# LPCDuino.net
KiCad netlist of a schematic drawn in Altium Designer
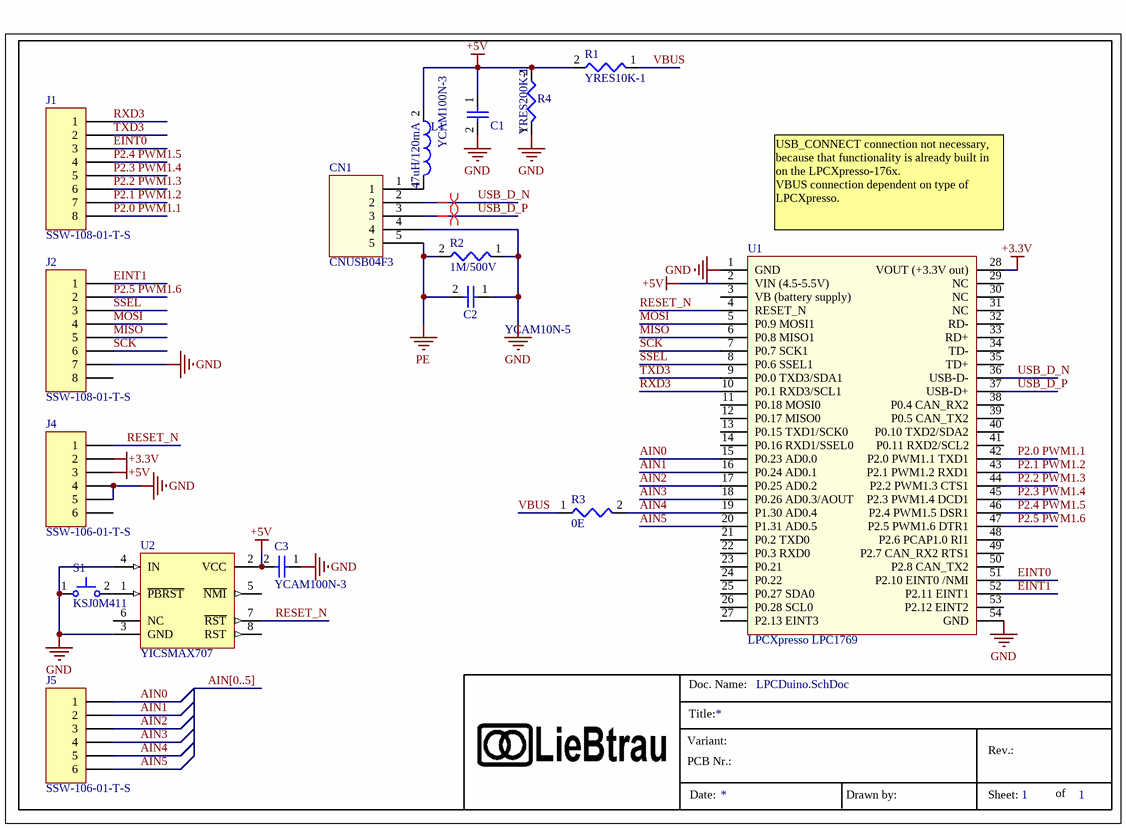
[diagram p0: LPCDuino.SchDoc]

(export (version "E")
  (design (tool "Eeschema 10.0.6"))
  (components
    (comp (ref "C1")
      (value "YCAM100N-3")
      (footprint "CA_0603")
      (libsource (lib "Testing") (part "CA_NONPOL"))
    )
    (comp (ref "C2")
      (value "YCAM10N-5")
      (footprint "CA_1206")
      (fields (field (name "MANUFACTURER") "Yageo (Phycomp)"))
      (libsource (lib "Testing") (part "CA_NONPOL"))
    )
    (comp (ref "C3")
      (value "YCAM100N-3")
      (footprint "CA_0603")
      (libsource (lib "Testing") (part "CA_NONPOL"))
    )
    (comp (ref "CN1")
      (value "CNUSB04F3")
      (footprint "CN_USB_B")
      (fields (field (name "MANUFACTURER") "TE Connectivity"))
      (libsource (lib "Testing") (part "CN_5P"))
    )
    (comp (ref "J1")
      (value "SSW-108-01-T-S")
      (footprint "CN_SOCKET8")
      (fields (field (name "MANUFACTURER") "Samtec"))
      (libsource (lib "Testing") (part "CN_8P"))
    )
    (comp (ref "J2")
      (value "SSW-108-01-T-S")
      (footprint "CN_SOCKET8")
      (fields (field (name "MANUFACTURER") "Samtec"))
      (libsource (lib "Testing") (part "CN_8P"))
    )
    (comp (ref "J4")
      (value "SSW-106-01-T-S")
      (footprint "CN_SOCKET6")
      (fields (field (name "MANUFACTURER") "Samtec"))
      (libsource (lib "Testing") (part "CN_6P"))
    )
    (comp (ref "J5")
      (value "SSW-106-01-T-S")
      (footprint "CN_SOCKET6")
      (fields (field (name "MANUFACTURER") "Samtec"))
      (libsource (lib "Testing") (part "CN_6P"))
    )
    (comp (ref "L1")
      (value "47uH/120mA")
      (footprint "CL_0805")
      (fields (field (name "PART NUMBER") "L0805C470MDWIT") (field (name "MANUFACTURER") "Kemet"))
      (libsource (lib "Testing") (part "CL_COIL"))
    )
    (comp (ref "R1")
      (value "YRES10K-1")
      (footprint "RE_0603")
      (description "Resistor")
      (libsource (lib "Testing") (part "RE_RES"))
    )
    (comp (ref "R2")
      (value "1M/500V")
      (footprint "RE_2010")
      (description "Resistor")
      (fields (field (name "PART NUMBER") "LHVC2010-1MFT4") (field (name "MANUFACTURER") "Welwyn"))
      (libsource (lib "Testing") (part "RE_RES"))
    )
    (comp (ref "R3")
      (value "0E")
      (footprint "RE_1206")
      (description "Resistor")
      (fields (field (name "PART NUMBER") "YRES0E") (field (name "MANUFACTURER") "Vishay Draloric"))
      (libsource (lib "Testing") (part "RE_RES"))
    )
    (comp (ref "R4")
      (value "YRES200K-1")
      (footprint "RE_0603")
      (description "Resistor")
      (libsource (lib "Testing") (part "RE_RES"))
    )
    (comp (ref "S1")
      (value "KSJ0M411")
      (footprint "SW_KSJ-M")
      (fields (field (name "MANUFACTURER") "C&K"))
      (libsource (lib "Testing") (part "SW_SPST"))
    )
    (comp (ref "U1")
      (value "LPCXpresso LPC1769")
      (footprint "MD_LPCXpresso")
      (fields (field (name "PART NUMBER") "OM13000") (field (name "MANUFACTURER") "NXP"))
      (libsource (lib "Testing") (part "IC_LPCXpresso_LPC1769"))
    )
    (comp (ref "U2")
      (value "YICSMAX707")
      (footprint "SC_SOIC8")
      (fields (field (name "MANUFACTURER") "Maxim"))
      (libsource (lib "Testing") (part "IC_MAX707"))
    )
  )
  (nets
    (net (code "1") (name "+3.3V") (class "Default")
      (node (ref "J4") (pin "2") (pinfunction "2_2") (pintype "passive"))
      (node (ref "U1") (pin "28") (pinfunction "VOUT_(+3.3V_out)_28") (pintype "passive"))
    )
    (net (code "2") (name "+5V") (class "Default")
      (node (ref "C1") (pin "1") (pinfunction "1_1") (pintype "passive"))
      (node (ref "C3") (pin "2") (pinfunction "2_2") (pintype "passive"))
      (node (ref "J4") (pin "3") (pinfunction "3_3") (pintype "passive"))
      (node (ref "L1") (pin "2") (pinfunction "2_2") (pintype "passive"))
      (node (ref "R1") (pin "2") (pinfunction "2_2") (pintype "passive"))
      (node (ref "R4") (pin "2") (pinfunction "2_2") (pintype "passive"))
      (node (ref "U1") (pin "2") (pinfunction "VIN_(4.5-5.5V)_2") (pintype "passive"))
      (node (ref "U2") (pin "2") (pinfunction "VCC_2") (pintype "power_in"))
    )
    (net (code "3") (name "/AIN0") (class "Default")
      (node (ref "J5") (pin "1") (pinfunction "1_1") (pintype "passive"))
      (node (ref "U1") (pin "15") (pinfunction "P0.23_AD0.0_15") (pintype "passive"))
    )
    (net (code "4") (name "/AIN1") (class "Default")
      (node (ref "J5") (pin "2") (pinfunction "2_2") (pintype "passive"))
      (node (ref "U1") (pin "16") (pinfunction "P0.24_AD0.1_16") (pintype "passive"))
    )
    (net (code "5") (name "/AIN2") (class "Default")
      (node (ref "J5") (pin "3") (pinfunction "3_3") (pintype "passive"))
      (node (ref "U1") (pin "17") (pinfunction "P0.25_AD0.2_17") (pintype "passive"))
    )
    (net (code "6") (name "/AIN3") (class "Default")
      (node (ref "J5") (pin "4") (pinfunction "4_4") (pintype "passive"))
      (node (ref "U1") (pin "18") (pinfunction "P0.26_AD0.3/AOUT_18") (pintype "passive"))
    )
    (net (code "7") (name "/AIN4") (class "Default")
      (node (ref "J5") (pin "5") (pinfunction "5_5") (pintype "passive"))
      (node (ref "R3") (pin "2") (pinfunction "2_2") (pintype "passive"))
      (node (ref "U1") (pin "19") (pinfunction "P1.30_AD0.4_19") (pintype "passive"))
    )
    (net (code "8") (name "/AIN5") (class "Default")
      (node (ref "J5") (pin "6") (pinfunction "6_6") (pintype "passive"))
      (node (ref "U1") (pin "20") (pinfunction "P1.31_AD0.5_20") (pintype "passive"))
    )
    (net (code "10") (name "/EINT0") (class "Default")
      (node (ref "J1") (pin "3") (pinfunction "3_3") (pintype "passive"))
      (node (ref "U1") (pin "51") (pinfunction "P2.10_EINT0_/NMI_51") (pintype "passive"))
    )
    (net (code "11") (name "/EINT1") (class "Default")
      (node (ref "J2") (pin "1") (pinfunction "1_1") (pintype "passive"))
      (node (ref "U1") (pin "52") (pinfunction "P2.11_EINT1_52") (pintype "passive"))
    )
    (net (code "12") (name "/MISO") (class "Default")
      (node (ref "J2") (pin "5") (pinfunction "5_5") (pintype "passive"))
      (node (ref "U1") (pin "6") (pinfunction "P0.8_MISO1_6") (pintype "passive"))
    )
    (net (code "13") (name "/MOSI") (class "Default")
      (node (ref "J2") (pin "4") (pinfunction "4_4") (pintype "passive"))
      (node (ref "U1") (pin "5") (pinfunction "P0.9_MOSI1_5") (pintype "passive"))
    )
    (net (code "14") (name "/P2.0 PWM1.1") (class "Default")
      (node (ref "J1") (pin "8") (pinfunction "8_8") (pintype "passive"))
      (node (ref "U1") (pin "42") (pinfunction "P2.0_PWM1.1_TXD1_42") (pintype "passive"))
    )
    (net (code "15") (name "/P2.1 PWM1.2") (class "Default")
      (node (ref "J1") (pin "7") (pinfunction "7_7") (pintype "passive"))
      (node (ref "U1") (pin "43") (pinfunction "P2.1_PWM1.2_RXD1_43") (pintype "passive"))
    )
    (net (code "16") (name "/P2.2 PWM1.3") (class "Default")
      (node (ref "J1") (pin "6") (pinfunction "6_6") (pintype "passive"))
      (node (ref "U1") (pin "44") (pinfunction "P2.2_PWM1.3_CTS1_44") (pintype "passive"))
    )
    (net (code "17") (name "/P2.3 PWM1.4") (class "Default")
      (node (ref "J1") (pin "5") (pinfunction "5_5") (pintype "passive"))
      (node (ref "U1") (pin "45") (pinfunction "P2.3_PWM1.4_DCD1_45") (pintype "passive"))
    )
    (net (code "18") (name "/P2.4 PWM1.5") (class "Default")
      (node (ref "J1") (pin "4") (pinfunction "4_4") (pintype "passive"))
      (node (ref "U1") (pin "46") (pinfunction "P2.4_PWM1.5_DSR1_46") (pintype "passive"))
    )
    (net (code "19") (name "/P2.5 PWM1.6") (class "Default")
      (node (ref "J2") (pin "2") (pinfunction "2_2") (pintype "passive"))
      (node (ref "U1") (pin "47") (pinfunction "P2.5_PWM1.6_DTR1_47") (pintype "passive"))
    )
    (net (code "20") (name "/RESET_N") (class "Default")
      (node (ref "J4") (pin "1") (pinfunction "1_1") (pintype "passive"))
      (node (ref "U1") (pin "4") (pinfunction "RESET_N_4") (pintype "passive"))
      (node (ref "U2") (pin "7") (pinfunction "~{RST}_7") (pintype "output"))
    )
    (net (code "21") (name "/RXD3") (class "Default")
      (node (ref "J1") (pin "1") (pinfunction "1_1") (pintype "passive"))
      (node (ref "U1") (pin "10") (pinfunction "P0.1_RXD3/SCL1_10") (pintype "passive"))
    )
    (net (code "22") (name "/SCK") (class "Default")
      (node (ref "J2") (pin "6") (pinfunction "6_6") (pintype "passive"))
      (node (ref "U1") (pin "7") (pinfunction "P0.7_SCK1_7") (pintype "passive"))
    )
    (net (code "23") (name "/SSEL") (class "Default")
      (node (ref "J2") (pin "3") (pinfunction "3_3") (pintype "passive"))
      (node (ref "U1") (pin "8") (pinfunction "P0.6_SSEL1_8") (pintype "passive"))
    )
    (net (code "24") (name "/TXD3") (class "Default")
      (node (ref "J1") (pin "2") (pinfunction "2_2") (pintype "passive"))
      (node (ref "U1") (pin "9") (pinfunction "P0.0_TXD3/SDA1_9") (pintype "passive"))
    )
    (net (code "25") (name "/USB_D_N") (class "Default")
      (node (ref "CN1") (pin "2") (pinfunction "2_2") (pintype "passive"))
      (node (ref "U1") (pin "36") (pinfunction "USB-D-_36") (pintype "passive"))
    )
    (net (code "26") (name "/USB_D_P") (class "Default")
      (node (ref "CN1") (pin "3") (pinfunction "3_3") (pintype "passive"))
      (node (ref "U1") (pin "37") (pinfunction "USB-D+_37") (pintype "passive"))
    )
    (net (code "27") (name "/VBUS") (class "Default")
      (node (ref "R1") (pin "1") (pinfunction "1_1") (pintype "passive"))
      (node (ref "R3") (pin "1") (pinfunction "1_1") (pintype "passive"))
    )
    (net (code "28") (name "GND") (class "Default")
      (node (ref "C1") (pin "2") (pinfunction "2_2") (pintype "passive"))
      (node (ref "C2") (pin "1") (pinfunction "1_1") (pintype "passive"))
      (node (ref "C3") (pin "1") (pinfunction "1_1") (pintype "passive"))
      (node (ref "CN1") (pin "4") (pinfunction "4_4") (pintype "passive"))
      (node (ref "J2") (pin "7") (pinfunction "7_7") (pintype "passive"))
      (node (ref "J4") (pin "4") (pinfunction "4_4") (pintype "passive"))
      (node (ref "J4") (pin "5") (pinfunction "5_5") (pintype "passive"))
      (node (ref "R2") (pin "1") (pinfunction "1_1") (pintype "passive"))
      (node (ref "R4") (pin "1") (pinfunction "1_1") (pintype "passive"))
      (node (ref "S1") (pin "1") (pinfunction "1_1") (pintype "passive"))
      (node (ref "U1") (pin "1") (pinfunction "GND_1") (pintype "passive"))
      (node (ref "U1") (pin "54") (pinfunction "GND_54") (pintype "passive"))
      (node (ref "U2") (pin "3") (pinfunction "GND_3") (pintype "power_in"))
      (node (ref "U2") (pin "4") (pinfunction "IN_4") (pintype "input"))
    )
    (net (code "29") (name "Net-(CN1-Pad1)") (class "Default")
      (node (ref "CN1") (pin "1") (pinfunction "1_1") (pintype "passive"))
      (node (ref "L1") (pin "1") (pinfunction "1_1") (pintype "passive"))
    )
    (net (code "30") (name "Net-(U2-~{PBRST})") (class "Default")
      (node (ref "S1") (pin "2") (pinfunction "2_2") (pintype "passive"))
      (node (ref "U2") (pin "1") (pinfunction "~{PBRST}_1") (pintype "input"))
    )
    (net (code "31") (name "PE") (class "Default")
      (node (ref "C2") (pin "2") (pinfunction "2_2") (pintype "passive"))
      (node (ref "CN1") (pin "5") (pinfunction "5_5") (pintype "passive"))
      (node (ref "R2") (pin "2") (pinfunction "2_2") (pintype "passive"))
    )
    (net (code "32") (name "unconnected-(J2-Pad8)") (class "Default")
      (node (ref "J2") (pin "8") (pinfunction "8_8") (pintype "passive"))
    )
    (net (code "33") (name "unconnected-(J4-Pad6)") (class "Default")
      (node (ref "J4") (pin "6") (pinfunction "6_6") (pintype "passive"))
    )
    (net (code "34") (name "unconnected-(U1-NC-Pad29)") (class "Default")
      (node (ref "U1") (pin "29") (pinfunction "NC_29") (pintype "passive"))
    )
    (net (code "35") (name "unconnected-(U1-NC-Pad30)") (class "Default")
      (node (ref "U1") (pin "30") (pinfunction "NC_30") (pintype "passive"))
    )
    (net (code "36") (name "unconnected-(U1-NC-Pad31)") (class "Default")
      (node (ref "U1") (pin "31") (pinfunction "NC_31") (pintype "passive"))
    )
    (net (code "37") (name "unconnected-(U1-P0.2_TXD0-Pad21)") (class "Default")
      (node (ref "U1") (pin "21") (pinfunction "P0.2_TXD0_21") (pintype "passive"))
    )
    (net (code "38") (name "unconnected-(U1-P0.3_RXD0-Pad22)") (class "Default")
      (node (ref "U1") (pin "22") (pinfunction "P0.3_RXD0_22") (pintype "passive"))
    )
    (net (code "39") (name "unconnected-(U1-P0.4_CAN_RX2-Pad38)") (class "Default")
      (node (ref "U1") (pin "38") (pinfunction "P0.4_CAN_RX2_38") (pintype "passive"))
    )
    (net (code "40") (name "unconnected-(U1-P0.5_CAN_TX2-Pad39)") (class "Default")
      (node (ref "U1") (pin "39") (pinfunction "P0.5_CAN_TX2_39") (pintype "passive"))
    )
    (net (code "41") (name "unconnected-(U1-P0.10_TXD2{slash}SDA2-Pad40)") (class "Default")
      (node (ref "U1") (pin "40") (pinfunction "P0.10_TXD2/SDA2_40") (pintype "passive"))
    )
    (net (code "42") (name "unconnected-(U1-P0.11_RXD2{slash}SCL2-Pad41)") (class "Default")
      (node (ref "U1") (pin "41") (pinfunction "P0.11_RXD2/SCL2_41") (pintype "passive"))
    )
    (net (code "43") (name "unconnected-(U1-P0.15_TXD1{slash}SCK0-Pad13)") (class "Default")
      (node (ref "U1") (pin "13") (pinfunction "P0.15_TXD1/SCK0_13") (pintype "passive"))
    )
    (net (code "44") (name "unconnected-(U1-P0.16_RXD1{slash}SSEL0-Pad14)") (class "Default")
      (node (ref "U1") (pin "14") (pinfunction "P0.16_RXD1/SSEL0_14") (pintype "passive"))
    )
    (net (code "45") (name "unconnected-(U1-P0.17_MISO0-Pad12)") (class "Default")
      (node (ref "U1") (pin "12") (pinfunction "P0.17_MISO0_12") (pintype "passive"))
    )
    (net (code "46") (name "unconnected-(U1-P0.18_MOSI0-Pad11)") (class "Default")
      (node (ref "U1") (pin "11") (pinfunction "P0.18_MOSI0_11") (pintype "passive"))
    )
    (net (code "47") (name "unconnected-(U1-P0.21-Pad23)") (class "Default")
      (node (ref "U1") (pin "23") (pinfunction "P0.21_23") (pintype "passive"))
    )
    (net (code "48") (name "unconnected-(U1-P0.22-Pad24)") (class "Default")
      (node (ref "U1") (pin "24") (pinfunction "P0.22_24") (pintype "passive"))
    )
    (net (code "49") (name "unconnected-(U1-P0.27_SDA0-Pad25)") (class "Default")
      (node (ref "U1") (pin "25") (pinfunction "P0.27_SDA0_25") (pintype "passive"))
    )
    (net (code "50") (name "unconnected-(U1-P0.28_SCL0-Pad26)") (class "Default")
      (node (ref "U1") (pin "26") (pinfunction "P0.28_SCL0_26") (pintype "passive"))
    )
    (net (code "51") (name "unconnected-(U1-P2.6_PCAP1.0_RI1-Pad48)") (class "Default")
      (node (ref "U1") (pin "48") (pinfunction "P2.6_PCAP1.0_RI1_48") (pintype "passive"))
    )
    (net (code "52") (name "unconnected-(U1-P2.7_CAN_RX2_RTS1-Pad49)") (class "Default")
      (node (ref "U1") (pin "49") (pinfunction "P2.7_CAN_RX2_RTS1_49") (pintype "passive"))
    )
    (net (code "53") (name "unconnected-(U1-P2.8_CAN_TX2-Pad50)") (class "Default")
      (node (ref "U1") (pin "50") (pinfunction "P2.8_CAN_TX2_50") (pintype "passive"))
    )
    (net (code "54") (name "unconnected-(U1-P2.12_EINT2-Pad53)") (class "Default")
      (node (ref "U1") (pin "53") (pinfunction "P2.12_EINT2_53") (pintype "passive"))
    )
    (net (code "55") (name "unconnected-(U1-P2.13_EINT3-Pad27)") (class "Default")
      (node (ref "U1") (pin "27") (pinfunction "P2.13_EINT3_27") (pintype "passive"))
    )
    (net (code "56") (name "unconnected-(U1-RD+-Pad33)") (class "Default")
      (node (ref "U1") (pin "33") (pinfunction "RD+_33") (pintype "passive"))
    )
    (net (code "57") (name "unconnected-(U1-RD--Pad32)") (class "Default")
      (node (ref "U1") (pin "32") (pinfunction "RD-_32") (pintype "passive"))
    )
    (net (code "58") (name "unconnected-(U1-TD+-Pad35)") (class "Default")
      (node (ref "U1") (pin "35") (pinfunction "TD+_35") (pintype "passive"))
    )
    (net (code "59") (name "unconnected-(U1-TD--Pad34)") (class "Default")
      (node (ref "U1") (pin "34") (pinfunction "TD-_34") (pintype "passive"))
    )
    (net (code "60") (name "unconnected-(U1-VB_(battery_supply)-Pad3)") (class "Default")
      (node (ref "U1") (pin "3") (pinfunction "VB_(battery_supply)_3") (pintype "passive"))
    )
    (net (code "61") (name "unconnected-(U2-NC-Pad6)") (class "Default")
      (node (ref "U2") (pin "6") (pinfunction "NC_6") (pintype "passive"))
    )
    (net (code "62") (name "unconnected-(U2-RST-Pad8)") (class "Default")
      (node (ref "U2") (pin "8") (pinfunction "RST_8") (pintype "output"))
    )
    (net (code "63") (name "unconnected-(U2-~{NMI}-Pad5)") (class "Default")
      (node (ref "U2") (pin "5") (pinfunction "~{NMI}_5") (pintype "output"))
    )
  )
)
